# Power.net
KiCad netlist of a schematic drawn in Altium Designer
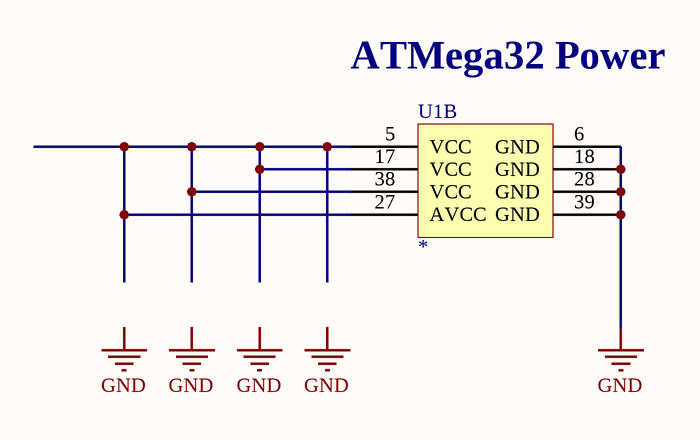
[diagram p0: Power.SchDoc]

(export (version "E")
  (design (tool "Eeschema 10.0.6"))
  (components (comp (ref "U1") (value "*") (libsource (lib "Parts") (part "ATmega32"))))
  (nets
    (net (code "1") (name "GND") (class "Default")
      (node (ref "U1") (pin "18") (pinfunction "GND_18") (pintype "passive"))
      (node (ref "U1") (pin "28") (pinfunction "GND_28") (pintype "passive"))
      (node (ref "U1") (pin "39") (pinfunction "GND_39") (pintype "passive"))
      (node (ref "U1") (pin "6") (pinfunction "GND_6") (pintype "passive"))
    )
    (net (code "2") (name "Net-(U1B-AVCC)") (class "Default")
      (node (ref "U1") (pin "17") (pinfunction "VCC_17") (pintype "passive"))
      (node (ref "U1") (pin "27") (pinfunction "AVCC_27") (pintype "passive"))
      (node (ref "U1") (pin "38") (pinfunction "VCC_38") (pintype "passive"))
      (node (ref "U1") (pin "5") (pinfunction "VCC_5") (pintype "passive"))
    )
  )
)
